# DAC_Filter.net
KiCad netlist of a schematic drawn in Altium Designer
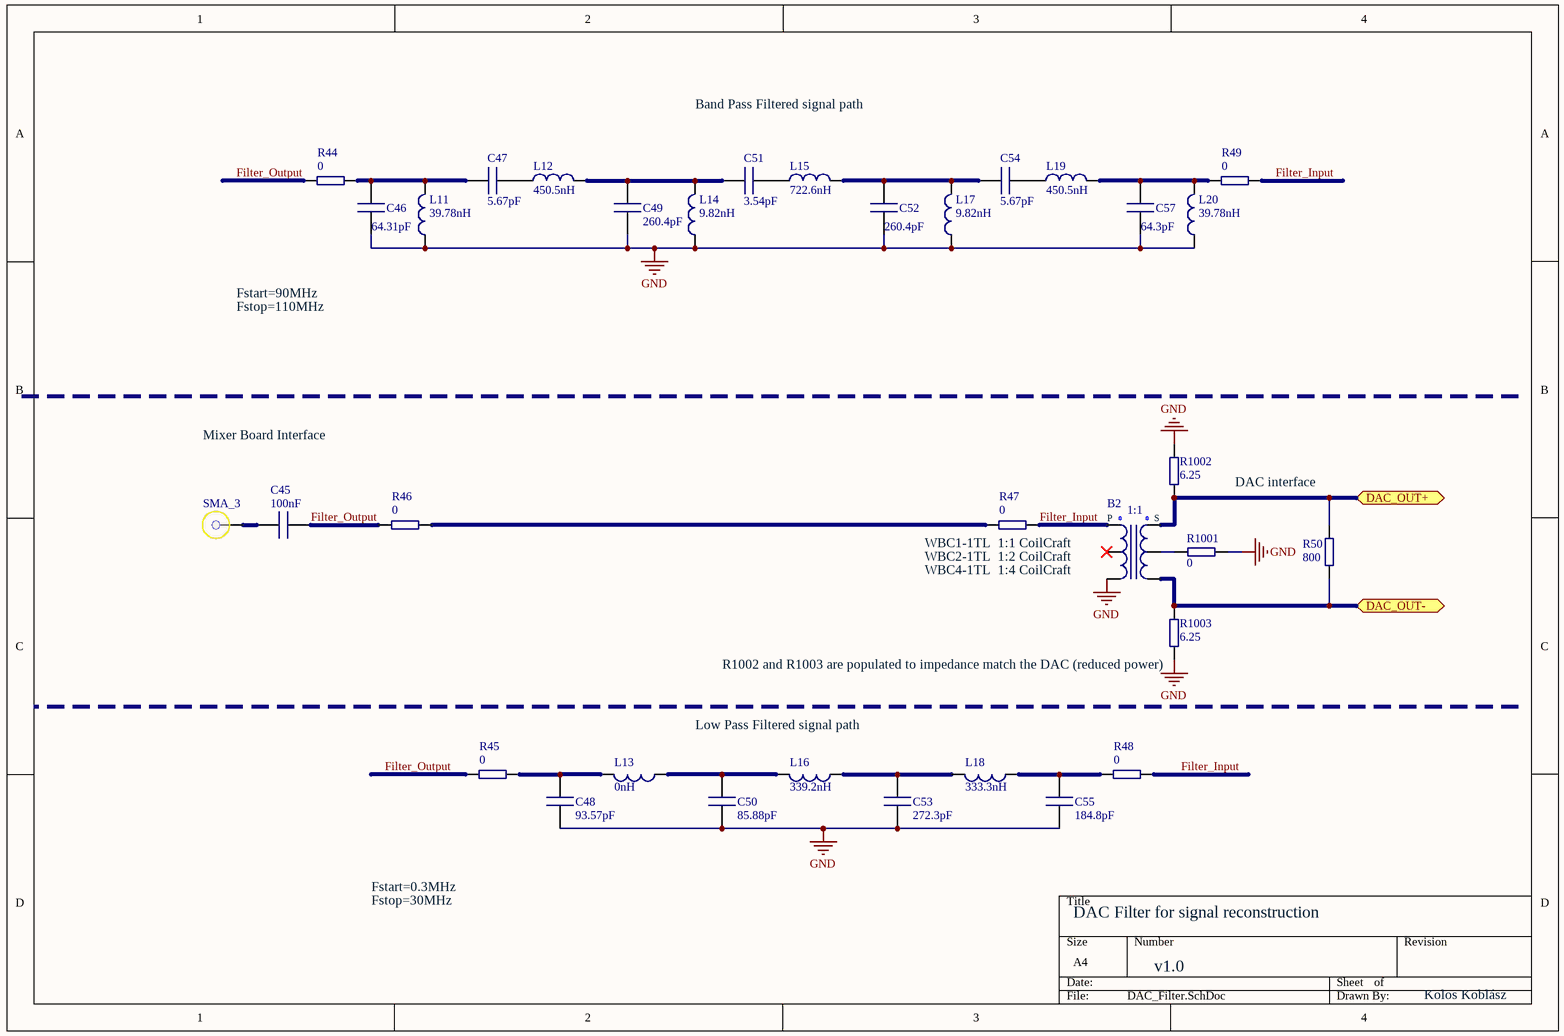
[diagram p0: DAC_Filter.SchDoc]

(export (version "E")
  (design (tool "Eeschema 10.0.6"))
  (components
    (comp (ref "B2")
      (value "Balun")
      (footprint "Balun_Coil_Craft_WBC")
      (description "SMD Balun")
      (fields
        (field (name "IMPEDANCETRANSFORMATION P : S") "1:1")
        (field (name "MANUFACTURER") "CoilCraft")
        (field (name "PARTNUMBER") "WBC1-1TL")
      )
      (libsource (lib "RadioProjectSchLib") (part "Balun3"))
    )
    (comp (ref "C45")
      (value "100nF")
      (footprint "0805 SMD Passive")
      (description "SMD Capacitor")
      (fields (field (name "Comment") "Cap1"))
      (libsource (lib "RadioProjectSchLib") (part "Cap1"))
    )
    (comp (ref "C46")
      (value "64.31pF")
      (footprint "0805 SMD Passive")
      (description "SMD Capacitor")
      (fields (field (name "Comment") "Cap1"))
      (libsource (lib "RadioProjectSchLib") (part "Cap1"))
    )
    (comp (ref "C47")
      (value "5.67pF")
      (footprint "0805 SMD Passive")
      (description "SMD Capacitor")
      (fields (field (name "Comment") "Cap1"))
      (libsource (lib "RadioProjectSchLib") (part "Cap1"))
    )
    (comp (ref "C48")
      (value "93.57pF")
      (footprint "0805 SMD Passive")
      (description "SMD Capacitor")
      (fields (field (name "Comment") "Cap1"))
      (libsource (lib "RadioProjectSchLib") (part "Cap1"))
    )
    (comp (ref "C49")
      (value "260.4pF")
      (footprint "0805 SMD Passive")
      (description "SMD Capacitor")
      (fields (field (name "Comment") "Cap1"))
      (libsource (lib "RadioProjectSchLib") (part "Cap1"))
    )
    (comp (ref "C50")
      (value "85.88pF")
      (footprint "0805 SMD Passive")
      (description "SMD Capacitor")
      (fields (field (name "Comment") "Cap1"))
      (libsource (lib "RadioProjectSchLib") (part "Cap1"))
    )
    (comp (ref "C51")
      (value "3.54pF")
      (footprint "0805 SMD Passive")
      (description "SMD Capacitor")
      (fields (field (name "Comment") "Cap1"))
      (libsource (lib "RadioProjectSchLib") (part "Cap1"))
    )
    (comp (ref "C52")
      (value "260.4pF")
      (footprint "0805 SMD Passive")
      (description "SMD Capacitor")
      (fields (field (name "Comment") "Cap1"))
      (libsource (lib "RadioProjectSchLib") (part "Cap1"))
    )
    (comp (ref "C53")
      (value "272.3pF")
      (footprint "0805 SMD Passive")
      (description "SMD Capacitor")
      (fields (field (name "Comment") "Cap1"))
      (libsource (lib "RadioProjectSchLib") (part "Cap1"))
    )
    (comp (ref "C54")
      (value "5.67pF")
      (footprint "0805 SMD Passive")
      (description "SMD Capacitor")
      (fields (field (name "Comment") "Cap1"))
      (libsource (lib "RadioProjectSchLib") (part "Cap1"))
    )
    (comp (ref "C55")
      (value "184.8pF")
      (footprint "0805 SMD Passive")
      (description "SMD Capacitor")
      (fields (field (name "Comment") "Cap1"))
      (libsource (lib "RadioProjectSchLib") (part "Cap1"))
    )
    (comp (ref "C57")
      (value "64.3pF")
      (footprint "0805 SMD Passive")
      (description "SMD Capacitor")
      (fields (field (name "Comment") "Cap1"))
      (libsource (lib "RadioProjectSchLib") (part "Cap1"))
    )
    (comp (ref "L11")
      (value "39.78nH")
      (footprint "0805 SMD Passive")
      (description "SMD Inductor")
      (fields (field (name "Comment") "Inductor"))
      (libsource (lib "RadioProjectSchLib") (part "Ind1"))
    )
    (comp (ref "L12")
      (value "450.5nH")
      (footprint "0805 SMD Passive")
      (description "SMD Inductor")
      (fields (field (name "Comment") "Inductor"))
      (libsource (lib "RadioProjectSchLib") (part "Ind1"))
    )
    (comp (ref "L13")
      (value "0nH")
      (footprint "0805 SMD Passive")
      (description "SMD Inductor")
      (fields (field (name "Comment") "Inductor"))
      (libsource (lib "RadioProjectSchLib") (part "Ind1"))
    )
    (comp (ref "L14")
      (value "9.82nH")
      (footprint "0805 SMD Passive")
      (description "SMD Inductor")
      (fields (field (name "Comment") "Inductor"))
      (libsource (lib "RadioProjectSchLib") (part "Ind1"))
    )
    (comp (ref "L15")
      (value "722.6nH")
      (footprint "0805 SMD Passive")
      (description "SMD Inductor")
      (fields (field (name "Comment") "Inductor"))
      (libsource (lib "RadioProjectSchLib") (part "Ind1"))
    )
    (comp (ref "L16")
      (value "339.2nH")
      (footprint "0805 SMD Passive")
      (description "SMD Inductor")
      (fields (field (name "Comment") "Inductor"))
      (libsource (lib "RadioProjectSchLib") (part "Ind1"))
    )
    (comp (ref "L17")
      (value "9.82nH")
      (footprint "0805 SMD Passive")
      (description "SMD Inductor")
      (fields (field (name "Comment") "Inductor"))
      (libsource (lib "RadioProjectSchLib") (part "Ind1"))
    )
    (comp (ref "L18")
      (value "333.3nH")
      (footprint "0805 SMD Passive")
      (description "SMD Inductor")
      (fields (field (name "Comment") "Inductor"))
      (libsource (lib "RadioProjectSchLib") (part "Ind1"))
    )
    (comp (ref "L19")
      (value "450.5nH")
      (footprint "0805 SMD Passive")
      (description "SMD Inductor")
      (fields (field (name "Comment") "Inductor"))
      (libsource (lib "RadioProjectSchLib") (part "Ind1"))
    )
    (comp (ref "L20")
      (value "39.78nH")
      (footprint "0805 SMD Passive")
      (description "SMD Inductor")
      (fields (field (name "Comment") "Inductor"))
      (libsource (lib "RadioProjectSchLib") (part "Ind1"))
    )
    (comp (ref "R44")
      (value "0")
      (footprint "0805 SMD Passive")
      (description "SMD Resistor")
      (fields (field (name "Comment") "Resistor"))
      (libsource (lib "RadioProjectSchLib") (part "Res1"))
    )
    (comp (ref "R45")
      (value "0")
      (footprint "0805 SMD Passive")
      (description "SMD Resistor")
      (fields (field (name "Comment") "Resistor"))
      (libsource (lib "RadioProjectSchLib") (part "Res1"))
    )
    (comp (ref "R46")
      (value "0")
      (footprint "0805 SMD Passive")
      (description "SMD Resistor")
      (fields (field (name "Comment") "Resistor"))
      (libsource (lib "RadioProjectSchLib") (part "Res1"))
    )
    (comp (ref "R47")
      (value "0")
      (footprint "0805 SMD Passive")
      (description "SMD Resistor")
      (fields (field (name "Comment") "Resistor"))
      (libsource (lib "RadioProjectSchLib") (part "Res1"))
    )
    (comp (ref "R48")
      (value "0")
      (footprint "0805 SMD Passive")
      (description "SMD Resistor")
      (fields (field (name "Comment") "Resistor"))
      (libsource (lib "RadioProjectSchLib") (part "Res1"))
    )
    (comp (ref "R49")
      (value "0")
      (footprint "0805 SMD Passive")
      (description "SMD Resistor")
      (fields (field (name "Comment") "Resistor"))
      (libsource (lib "RadioProjectSchLib") (part "Res1"))
    )
    (comp (ref "R50")
      (value "800")
      (footprint "0805 SMD Passive")
      (description "SMD Resistor")
      (fields (field (name "Comment") "Resistor"))
      (libsource (lib "RadioProjectSchLib") (part "Res1"))
    )
    (comp (ref "R1001")
      (value "0")
      (footprint "0805 SMD Passive")
      (description "SMD Resistor")
      (fields (field (name "Comment") "Resistor"))
      (libsource (lib "RadioProjectSchLib") (part "Res1"))
    )
    (comp (ref "R1002")
      (value "6.25")
      (footprint "0805 SMD Passive")
      (description "SMD Resistor")
      (fields (field (name "Comment") "Resistor"))
      (libsource (lib "RadioProjectSchLib") (part "Res1"))
    )
    (comp (ref "R1003")
      (value "6.25")
      (footprint "0805 SMD Passive")
      (description "SMD Resistor")
      (fields (field (name "Comment") "Resistor"))
      (libsource (lib "RadioProjectSchLib") (part "Res1"))
    )
    (comp (ref "SMA_3")
      (value "SMA1")
      (footprint "SMA Flange")
      (description "SMA Female")
      (libsource (lib "RadioProjectSchLib") (part "SMA1"))
    )
  )
  (nets
    (net (code "1") (name "/DAC_OUT+") (class "Default")
      (node (ref "B2") (pin "1") (pinfunction "1_1") (pintype "passive"))
      (node (ref "R1002") (pin "1") (pinfunction "*_1") (pintype "passive"))
      (node (ref "R50") (pin "2") (pinfunction "*_2") (pintype "passive"))
    )
    (net (code "2") (name "/DAC_OUT-") (class "Default")
      (node (ref "B2") (pin "3") (pinfunction "3_3") (pintype "passive"))
      (node (ref "R1003") (pin "1") (pinfunction "*_1") (pintype "passive"))
      (node (ref "R50") (pin "1") (pinfunction "*_1") (pintype "passive"))
    )
    (net (code "3") (name "/Filter_Input") (class "Default")
      (node (ref "B2") (pin "6") (pinfunction "6_6") (pintype "passive"))
      (node (ref "R47") (pin "1") (pinfunction "*_1") (pintype "passive"))
      (node (ref "R48") (pin "1") (pinfunction "*_1") (pintype "passive"))
      (node (ref "R49") (pin "1") (pinfunction "*_1") (pintype "passive"))
    )
    (net (code "4") (name "/Filter_Output") (class "Default")
      (node (ref "C45") (pin "1") (pinfunction "*_1") (pintype "passive"))
      (node (ref "R44") (pin "2") (pinfunction "*_2") (pintype "passive"))
      (node (ref "R45") (pin "2") (pinfunction "*_2") (pintype "passive"))
      (node (ref "R46") (pin "1") (pinfunction "*_1") (pintype "passive"))
    )
    (net (code "5") (name "GND") (class "Default")
      (node (ref "B2") (pin "4") (pinfunction "4_4") (pintype "passive"))
      (node (ref "C46") (pin "2") (pinfunction "*_2") (pintype "passive"))
      (node (ref "C48") (pin "1") (pinfunction "*_1") (pintype "passive"))
      (node (ref "C49") (pin "2") (pinfunction "*_2") (pintype "passive"))
      (node (ref "C50") (pin "1") (pinfunction "*_1") (pintype "passive"))
      (node (ref "C52") (pin "2") (pinfunction "*_2") (pintype "passive"))
      (node (ref "C53") (pin "1") (pinfunction "*_1") (pintype "passive"))
      (node (ref "C55") (pin "1") (pinfunction "*_1") (pintype "passive"))
      (node (ref "C57") (pin "2") (pinfunction "*_2") (pintype "passive"))
      (node (ref "L11") (pin "1") (pinfunction "*_1") (pintype "passive"))
      (node (ref "L14") (pin "1") (pinfunction "*_1") (pintype "passive"))
      (node (ref "L17") (pin "1") (pinfunction "*_1") (pintype "passive"))
      (node (ref "L20") (pin "1") (pinfunction "*_1") (pintype "passive"))
      (node (ref "R1001") (pin "2") (pinfunction "*_2") (pintype "passive"))
      (node (ref "R1002") (pin "2") (pinfunction "*_2") (pintype "passive"))
      (node (ref "R1003") (pin "2") (pinfunction "*_2") (pintype "passive"))
    )
    (net (code "6") (name "Net-(B2-Pad2)") (class "Default")
      (node (ref "B2") (pin "2") (pinfunction "2_2") (pintype "passive"))
      (node (ref "R1001") (pin "1") (pinfunction "*_1") (pintype "passive"))
    )
    (net (code "7") (name "Net-(C45-*-Pad2)") (class "Default")
      (node (ref "C45") (pin "2") (pinfunction "*_2") (pintype "passive"))
      (node (ref "SMA_3") (pin "1") (pinfunction "1_1") (pintype "passive"))
    )
    (net (code "8") (name "Net-(C46-*-Pad1)") (class "Default")
      (node (ref "C46") (pin "1") (pinfunction "*_1") (pintype "passive"))
      (node (ref "C47") (pin "1") (pinfunction "*_1") (pintype "passive"))
      (node (ref "L11") (pin "2") (pinfunction "*_2") (pintype "passive"))
      (node (ref "R44") (pin "1") (pinfunction "*_1") (pintype "passive"))
    )
    (net (code "9") (name "Net-(C47-*-Pad2)") (class "Default")
      (node (ref "C47") (pin "2") (pinfunction "*_2") (pintype "passive"))
      (node (ref "L12") (pin "1") (pinfunction "*_1") (pintype "passive"))
    )
    (net (code "10") (name "Net-(C48-*-Pad2)") (class "Default")
      (node (ref "C48") (pin "2") (pinfunction "*_2") (pintype "passive"))
      (node (ref "L13") (pin "2") (pinfunction "*_2") (pintype "passive"))
      (node (ref "R45") (pin "1") (pinfunction "*_1") (pintype "passive"))
    )
    (net (code "11") (name "Net-(C49-*-Pad1)") (class "Default")
      (node (ref "C49") (pin "1") (pinfunction "*_1") (pintype "passive"))
      (node (ref "C51") (pin "1") (pinfunction "*_1") (pintype "passive"))
      (node (ref "L12") (pin "2") (pinfunction "*_2") (pintype "passive"))
      (node (ref "L14") (pin "2") (pinfunction "*_2") (pintype "passive"))
    )
    (net (code "12") (name "Net-(C50-*-Pad2)") (class "Default")
      (node (ref "C50") (pin "2") (pinfunction "*_2") (pintype "passive"))
      (node (ref "L13") (pin "1") (pinfunction "*_1") (pintype "passive"))
      (node (ref "L16") (pin "2") (pinfunction "*_2") (pintype "passive"))
    )
    (net (code "13") (name "Net-(C51-*-Pad2)") (class "Default")
      (node (ref "C51") (pin "2") (pinfunction "*_2") (pintype "passive"))
      (node (ref "L15") (pin "1") (pinfunction "*_1") (pintype "passive"))
    )
    (net (code "14") (name "Net-(C52-*-Pad1)") (class "Default")
      (node (ref "C52") (pin "1") (pinfunction "*_1") (pintype "passive"))
      (node (ref "C54") (pin "1") (pinfunction "*_1") (pintype "passive"))
      (node (ref "L15") (pin "2") (pinfunction "*_2") (pintype "passive"))
      (node (ref "L17") (pin "2") (pinfunction "*_2") (pintype "passive"))
    )
    (net (code "15") (name "Net-(C53-*-Pad2)") (class "Default")
      (node (ref "C53") (pin "2") (pinfunction "*_2") (pintype "passive"))
      (node (ref "L16") (pin "1") (pinfunction "*_1") (pintype "passive"))
      (node (ref "L18") (pin "2") (pinfunction "*_2") (pintype "passive"))
    )
    (net (code "16") (name "Net-(C54-*-Pad2)") (class "Default")
      (node (ref "C54") (pin "2") (pinfunction "*_2") (pintype "passive"))
      (node (ref "L19") (pin "1") (pinfunction "*_1") (pintype "passive"))
    )
    (net (code "17") (name "Net-(C55-*-Pad2)") (class "Default")
      (node (ref "C55") (pin "2") (pinfunction "*_2") (pintype "passive"))
      (node (ref "L18") (pin "1") (pinfunction "*_1") (pintype "passive"))
      (node (ref "R48") (pin "2") (pinfunction "*_2") (pintype "passive"))
    )
    (net (code "18") (name "Net-(C57-*-Pad1)") (class "Default")
      (node (ref "C57") (pin "1") (pinfunction "*_1") (pintype "passive"))
      (node (ref "L19") (pin "2") (pinfunction "*_2") (pintype "passive"))
      (node (ref "L20") (pin "2") (pinfunction "*_2") (pintype "passive"))
      (node (ref "R49") (pin "2") (pinfunction "*_2") (pintype "passive"))
    )
    (net (code "19") (name "Net-(R46-*-Pad2)") (class "Default")
      (node (ref "R46") (pin "2") (pinfunction "*_2") (pintype "passive"))
      (node (ref "R47") (pin "2") (pinfunction "*_2") (pintype "passive"))
    )
    (net (code "20") (name "unconnected-(B2-Pad5)") (class "Default")
      (node (ref "B2") (pin "5") (pinfunction "5_5") (pintype "passive+no_connect"))
    )
  )
)
